# MySXActuator.net
KiCad netlist of a schematic drawn in EAGLE
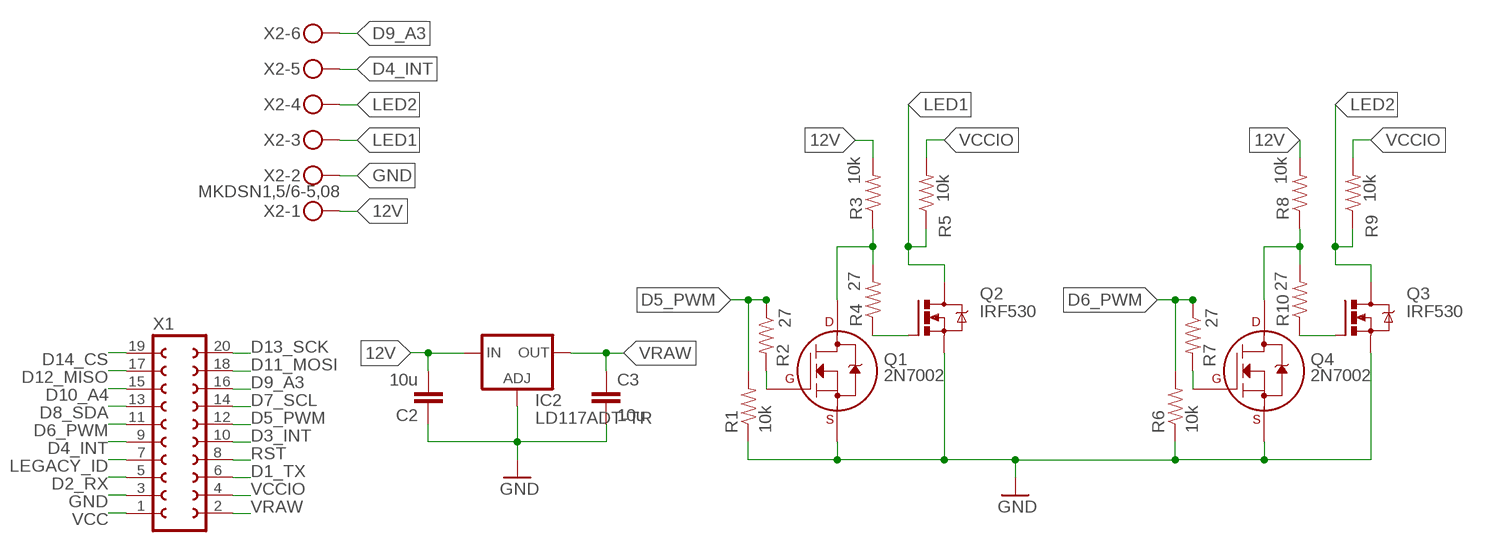
[diagram p0: schematic, sheet 1]

(export (version "E")
  (design (tool "Eeschema 10.0.6"))
  (components
    (comp (ref "C2")
      (value "10u")
      (footprint "eagle-import:1206")
      (libsource (lib "eagle-import") (part "CAP1206"))
    )
    (comp (ref "C3")
      (value "10u")
      (footprint "eagle-import:0603-CAP")
      (libsource (lib "eagle-import") (part "CAP0603-CAP"))
    )
    (comp (ref "IC2")
      (value "LD117ADT-TR")
      (footprint "eagle-import:DPACK")
      (libsource (lib "eagle-import") (part "LD117A?DT-TR"))
    )
    (comp (ref "Q1")
      (value "2N7002")
      (footprint "eagle-import:SOT-23")
      (libsource (lib "eagle-import") (part "2N700_SOT232"))
    )
    (comp (ref "Q2")
      (value "IRF530")
      (footprint "eagle-import:TO220BV")
      (libsource (lib "eagle-import") (part "IRF530"))
    )
    (comp (ref "Q3")
      (value "IRF530")
      (footprint "eagle-import:TO220BV")
      (libsource (lib "eagle-import") (part "IRF530"))
    )
    (comp (ref "Q4")
      (value "2N7002")
      (footprint "eagle-import:SOT-23")
      (libsource (lib "eagle-import") (part "2N700_SOT232"))
    )
    (comp (ref "R1")
      (value "10k")
      (footprint "eagle-import:0603-RES")
      (libsource (lib "eagle-import") (part "RESISTOR0603-RES"))
    )
    (comp (ref "R2")
      (value "27")
      (footprint "eagle-import:0603-RES")
      (libsource (lib "eagle-import") (part "RESISTOR0603-RES"))
    )
    (comp (ref "R3")
      (value "10k")
      (footprint "eagle-import:0603-RES")
      (libsource (lib "eagle-import") (part "RESISTOR0603-RES"))
    )
    (comp (ref "R4")
      (value "27")
      (footprint "eagle-import:0603-RES")
      (libsource (lib "eagle-import") (part "RESISTOR0603-RES"))
    )
    (comp (ref "R5")
      (value "10k")
      (footprint "eagle-import:0603-RES")
      (libsource (lib "eagle-import") (part "RESISTOR0603-RES"))
    )
    (comp (ref "R6")
      (value "10k")
      (footprint "eagle-import:0603-RES")
      (libsource (lib "eagle-import") (part "RESISTOR0603-RES"))
    )
    (comp (ref "R7")
      (value "27")
      (footprint "eagle-import:0603-RES")
      (libsource (lib "eagle-import") (part "RESISTOR0603-RES"))
    )
    (comp (ref "R8")
      (value "10k")
      (footprint "eagle-import:0603-RES")
      (libsource (lib "eagle-import") (part "RESISTOR0603-RES"))
    )
    (comp (ref "R9")
      (value "10k")
      (footprint "eagle-import:0603-RES")
      (libsource (lib "eagle-import") (part "RESISTOR0603-RES"))
    )
    (comp (ref "R10")
      (value "27")
      (footprint "eagle-import:0603-RES")
      (libsource (lib "eagle-import") (part "RESISTOR0603-RES"))
    )
    (comp (ref "X1")
      (value "FE10-2")
      (footprint "eagle-import:FE10-2")
      (libsource (lib "eagle-import") (part "FE10-2"))
    )
    (comp (ref "X2")
      (value "MKDSN1,5/6-5,08")
      (footprint "eagle-import:MKDSN1,5_6-5,08")
      (libsource (lib "eagle-import") (part "MKDSN1,5/6-5,08"))
    )
  )
  (nets
    (net (code "1") (name "/D1_TX") (class "Default")
      (node (ref "X1") (pin "6") (pinfunction "6_6") (pintype "passive"))
    )
    (net (code "2") (name "/D2_RX") (class "Default")
      (node (ref "X1") (pin "5") (pinfunction "5_5") (pintype "passive"))
    )
    (net (code "3") (name "/D3_INT") (class "Default")
      (node (ref "X1") (pin "10") (pinfunction "10_10") (pintype "passive"))
    )
    (net (code "4") (name "/D7_SCL") (class "Default")
      (node (ref "X1") (pin "14") (pinfunction "14_14") (pintype "passive"))
    )
    (net (code "5") (name "/D8_SDA") (class "Default")
      (node (ref "X1") (pin "13") (pinfunction "13_13") (pintype "passive"))
    )
    (net (code "6") (name "/D10_A4") (class "Default")
      (node (ref "X1") (pin "15") (pinfunction "15_15") (pintype "passive"))
    )
    (net (code "7") (name "/D11_MOSI") (class "Default")
      (node (ref "X1") (pin "18") (pinfunction "18_18") (pintype "passive"))
    )
    (net (code "8") (name "/D12_MISO") (class "Default")
      (node (ref "X1") (pin "17") (pinfunction "17_17") (pintype "passive"))
    )
    (net (code "9") (name "/D13_SCK") (class "Default")
      (node (ref "X1") (pin "20") (pinfunction "20_20") (pintype "passive"))
    )
    (net (code "10") (name "/D14_CS") (class "Default")
      (node (ref "X1") (pin "19") (pinfunction "19_19") (pintype "passive"))
    )
    (net (code "11") (name "/LEGACY_ID") (class "Default")
      (node (ref "X1") (pin "7") (pinfunction "7_7") (pintype "passive"))
    )
    (net (code "12") (name "/RST") (class "Default")
      (node (ref "X1") (pin "8") (pinfunction "8_8") (pintype "passive"))
    )
    (net (code "13") (name "/VCC") (class "Default")
      (node (ref "X1") (pin "1") (pinfunction "1_1") (pintype "passive"))
    )
    (net (code "14") (name "12V") (class "Default")
      (node (ref "C2") (pin "2") (pinfunction "2_2") (pintype "passive"))
      (node (ref "IC2") (pin "3") (pinfunction "IN_3") (pintype "input"))
      (node (ref "R3") (pin "2") (pinfunction "2_2") (pintype "passive"))
      (node (ref "R8") (pin "2") (pinfunction "2_2") (pintype "passive"))
      (node (ref "X2") (pin "1") (pinfunction "KL_1") (pintype "passive"))
    )
    (net (code "15") (name "D4_INT") (class "Default")
      (node (ref "X1") (pin "9") (pinfunction "9_9") (pintype "passive"))
      (node (ref "X2") (pin "5") (pinfunction "KL_5") (pintype "passive"))
    )
    (net (code "16") (name "D5_PWM") (class "Default")
      (node (ref "R1") (pin "2") (pinfunction "2_2") (pintype "passive"))
      (node (ref "R2") (pin "1") (pinfunction "1_1") (pintype "passive"))
      (node (ref "X1") (pin "12") (pinfunction "12_12") (pintype "passive"))
    )
    (net (code "17") (name "D6_PWM") (class "Default")
      (node (ref "R6") (pin "2") (pinfunction "2_2") (pintype "passive"))
      (node (ref "R7") (pin "1") (pinfunction "1_1") (pintype "passive"))
      (node (ref "X1") (pin "11") (pinfunction "11_11") (pintype "passive"))
    )
    (net (code "18") (name "D9_A3") (class "Default")
      (node (ref "X1") (pin "16") (pinfunction "16_16") (pintype "passive"))
      (node (ref "X2") (pin "6") (pinfunction "KL_6") (pintype "passive"))
    )
    (net (code "19") (name "GND") (class "Default")
      (node (ref "C2") (pin "1") (pinfunction "1_1") (pintype "passive"))
      (node (ref "C3") (pin "2") (pinfunction "2_2") (pintype "passive"))
      (node (ref "IC2") (pin "1") (pinfunction "ADJ_1") (pintype "input"))
      (node (ref "Q1") (pin "2") (pinfunction "S_2") (pintype "bidirectional"))
      (node (ref "Q2") (pin "S") (pinfunction "S_S") (pintype "passive"))
      (node (ref "Q3") (pin "S") (pinfunction "S_S") (pintype "passive"))
      (node (ref "Q4") (pin "2") (pinfunction "S_2") (pintype "bidirectional"))
      (node (ref "R1") (pin "1") (pinfunction "1_1") (pintype "passive"))
      (node (ref "R6") (pin "1") (pinfunction "1_1") (pintype "passive"))
      (node (ref "X1") (pin "3") (pinfunction "3_3") (pintype "passive"))
      (node (ref "X2") (pin "2") (pinfunction "KL_2") (pintype "passive"))
    )
    (net (code "20") (name "LED1") (class "Default")
      (node (ref "Q2") (pin "D") (pinfunction "D_D") (pintype "passive"))
      (node (ref "R5") (pin "1") (pinfunction "1_1") (pintype "passive"))
      (node (ref "X2") (pin "3") (pinfunction "KL_3") (pintype "passive"))
    )
    (net (code "21") (name "LED2") (class "Default")
      (node (ref "Q3") (pin "D") (pinfunction "D_D") (pintype "passive"))
      (node (ref "R9") (pin "1") (pinfunction "1_1") (pintype "passive"))
      (node (ref "X2") (pin "4") (pinfunction "KL_4") (pintype "passive"))
    )
    (net (code "22") (name "Net-(Q1-D)") (class "Default")
      (node (ref "Q1") (pin "3") (pinfunction "D_3") (pintype "bidirectional"))
      (node (ref "R3") (pin "1") (pinfunction "1_1") (pintype "passive"))
      (node (ref "R4") (pin "2") (pinfunction "2_2") (pintype "passive"))
    )
    (net (code "23") (name "Net-(Q1-G)") (class "Default")
      (node (ref "Q1") (pin "1") (pinfunction "G_1") (pintype "tri_state"))
      (node (ref "R2") (pin "2") (pinfunction "2_2") (pintype "passive"))
    )
    (net (code "24") (name "Net-(Q2-PadG)") (class "Default")
      (node (ref "Q2") (pin "G") (pinfunction "G_G") (pintype "passive"))
      (node (ref "R4") (pin "1") (pinfunction "1_1") (pintype "passive"))
    )
    (net (code "25") (name "Net-(Q3-PadG)") (class "Default")
      (node (ref "Q3") (pin "G") (pinfunction "G_G") (pintype "passive"))
      (node (ref "R10") (pin "1") (pinfunction "1_1") (pintype "passive"))
    )
    (net (code "26") (name "Net-(Q4-D)") (class "Default")
      (node (ref "Q4") (pin "3") (pinfunction "D_3") (pintype "bidirectional"))
      (node (ref "R10") (pin "2") (pinfunction "2_2") (pintype "passive"))
      (node (ref "R8") (pin "1") (pinfunction "1_1") (pintype "passive"))
    )
    (net (code "27") (name "Net-(Q4-G)") (class "Default")
      (node (ref "Q4") (pin "1") (pinfunction "G_1") (pintype "tri_state"))
      (node (ref "R7") (pin "2") (pinfunction "2_2") (pintype "passive"))
    )
    (net (code "28") (name "VCCIO") (class "Default")
      (node (ref "R5") (pin "2") (pinfunction "2_2") (pintype "passive"))
      (node (ref "R9") (pin "2") (pinfunction "2_2") (pintype "passive"))
      (node (ref "X1") (pin "4") (pinfunction "4_4") (pintype "passive"))
    )
    (net (code "29") (name "VRAW") (class "Default")
      (node (ref "C3") (pin "1") (pinfunction "1_1") (pintype "passive"))
      (node (ref "IC2") (pin "4") (pinfunction "OUT_4") (pintype "passive"))
      (node (ref "X1") (pin "2") (pinfunction "2_2") (pintype "passive"))
    )
  )
)
